# line_follower.net
KiCad netlist of a schematic drawn in EAGLE
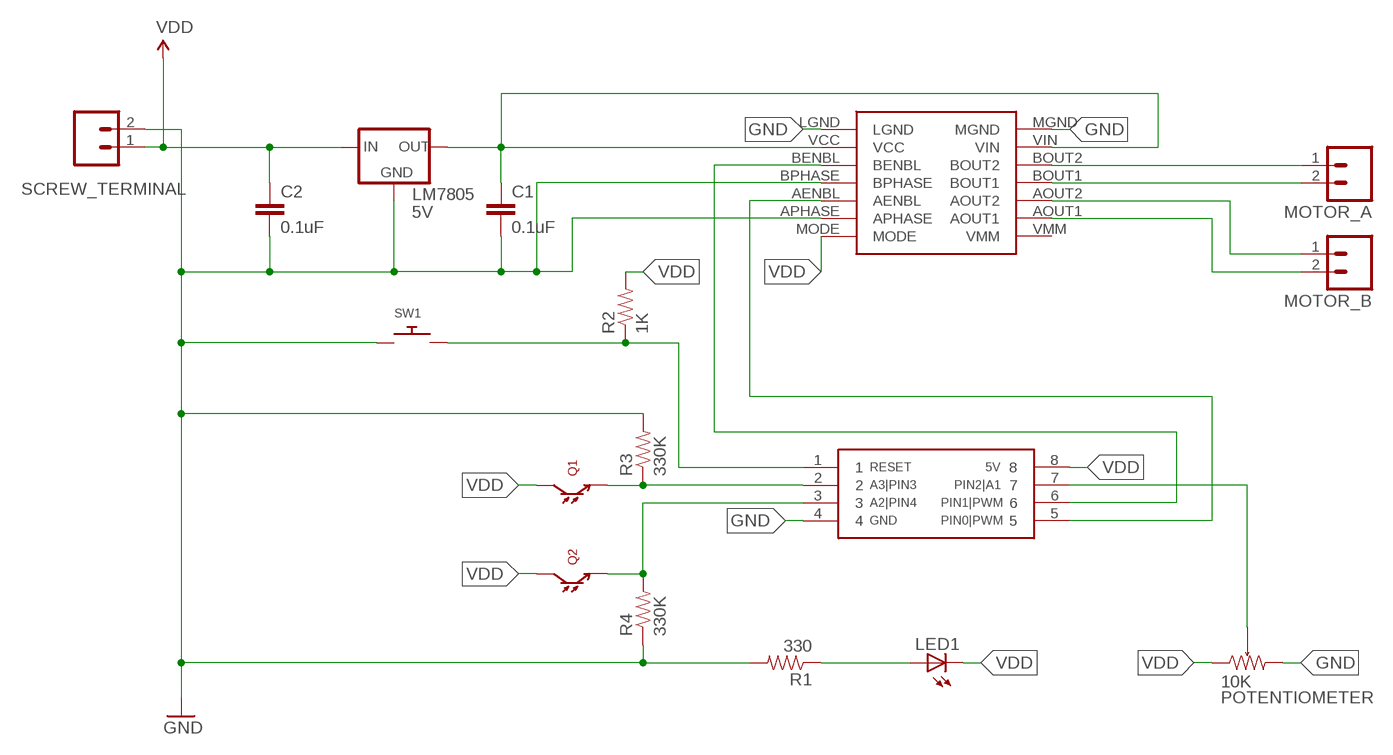
[diagram p0: schematic, sheet 1]

(export (version "E")
  (design (tool "Eeschema 10.0.6"))
  (components
    (comp (ref "10K")
      (value "POTENTIOMETER")
      (footprint "eagle-import:0603-ARV")
      (libsource (lib "eagle-import") (part "POTENTIOMETER"))
    )
    (comp (ref "ATTINY85")
      (value "ATTINY85")
      (footprint "eagle-import:ATTINY_DIP")
      (libsource (lib "eagle-import") (part "ATTINY85"))
    )
    (comp (ref "C1")
      (value "0.1uF")
      (footprint "eagle-import:CAP-PTH-SMALLEZ")
      (libsource (lib "eagle-import") (part "CAPEZ"))
    )
    (comp (ref "C2")
      (value "0.1uF")
      (footprint "eagle-import:CAP-PTH-SMALLEZ")
      (libsource (lib "eagle-import") (part "CAPEZ"))
    )
    (comp (ref "DRV8835")
      (value "POLOLU_MOTOR_DRV8835THROUGHHOLE")
      (footprint "eagle-import:POLOLU_MOTOR_DRV_DRV8835")
      (libsource (lib "eagle-import") (part "POLOLU_MOTOR_DRV8835THROUGHHOLE"))
    )
    (comp (ref "LED1")
      (value "LED5MM")
      (footprint "eagle-import:LED5MM")
      (libsource (lib "eagle-import") (part "LED5MM"))
    )
    (comp (ref "LM7805")
      (value "5V")
      (footprint "eagle-import:78XXS")
      (libsource (lib "eagle-import") (part "78XXS"))
    )
    (comp (ref "MOTOR_A")
      (value "M02PTH")
      (footprint "eagle-import:1X02")
      (libsource (lib "eagle-import") (part "M02PTH"))
    )
    (comp (ref "MOTOR_B")
      (value "M02PTH")
      (footprint "eagle-import:1X02")
      (libsource (lib "eagle-import") (part "M02PTH"))
    )
    (comp (ref "Q1")
      (value "LTR-301")
      (footprint "eagle-import:LTR-301")
      (libsource (lib "eagle-import") (part "LTR-301"))
    )
    (comp (ref "Q2")
      (value "LTR-301")
      (footprint "eagle-import:LTR-301")
      (libsource (lib "eagle-import") (part "LTR-301"))
    )
    (comp (ref "R1")
      (value "330")
      (footprint "eagle-import:AXIAL-0.3EZ")
      (libsource (lib "eagle-import") (part "RESISTOREZ"))
    )
    (comp (ref "R2")
      (value "1K")
      (footprint "eagle-import:AXIAL-0.3EZ")
      (libsource (lib "eagle-import") (part "RESISTOREZ"))
    )
    (comp (ref "R3")
      (value "330K")
      (footprint "eagle-import:AXIAL-0.3EZ")
      (libsource (lib "eagle-import") (part "RESISTOREZ"))
    )
    (comp (ref "R4")
      (value "330K")
      (footprint "eagle-import:AXIAL-0.3EZ")
      (libsource (lib "eagle-import") (part "RESISTOREZ"))
    )
    (comp (ref "SCREW_TERMINAL")
      (value "M02JST-PTH-VERT")
      (footprint "eagle-import:JST-2-PTH-VERT")
      (libsource (lib "eagle-import") (part "M02JST-PTH-VERT"))
    )
    (comp (ref "SW1")
      (value "SWITCH_PUSHBUTTONEVQ-PE")
      (footprint "eagle-import:TACT_PANA-EVQ")
      (libsource (lib "eagle-import") (part "SWITCH_PUSHBUTTONEVQ-PE"))
    )
  )
  (nets
    (net (code "1") (name "GND") (class "Default")
      (node (ref "10K") (pin "2") (pinfunction "2_2") (pintype "passive"))
      (node (ref "ATTINY85") (pin "4") (pinfunction "4_4") (pintype "bidirectional"))
      (node (ref "C1") (pin "2") (pinfunction "2_2") (pintype "passive"))
      (node (ref "C2") (pin "2") (pinfunction "2_2") (pintype "passive"))
      (node (ref "DRV8835") (pin "APHASE") (pinfunction "APHASE_APHASE") (pintype "bidirectional"))
      (node (ref "DRV8835") (pin "BPHASE") (pinfunction "BPHASE_BPHASE") (pintype "bidirectional"))
      (node (ref "DRV8835") (pin "LGND") (pinfunction "LGND_LGND") (pintype "bidirectional"))
      (node (ref "DRV8835") (pin "MGND") (pinfunction "MGND_MGND") (pintype "bidirectional"))
      (node (ref "LM7805") (pin "GND") (pinfunction "GND_GND") (pintype "input"))
      (node (ref "R1") (pin "P$2") (pinfunction "2_P$2") (pintype "passive"))
      (node (ref "R3") (pin "P$2") (pinfunction "2_P$2") (pintype "passive"))
      (node (ref "R4") (pin "P$1") (pinfunction "1_P$1") (pintype "passive"))
      (node (ref "SCREW_TERMINAL") (pin "2") (pinfunction "2_2") (pintype "passive"))
      (node (ref "SW1") (pin "P$1") (pinfunction "P$1_P$1") (pintype "passive"))
    )
    (net (code "2") (name "Net-(10K-P$1-Pad3)") (class "Default")
      (node (ref "10K") (pin "3") (pinfunction "P$1_3") (pintype "bidirectional"))
      (node (ref "10K") (pin "4") (pinfunction "P$1_4") (pintype "bidirectional"))
      (node (ref "10K") (pin "5") (pinfunction "P$1_5") (pintype "bidirectional"))
      (node (ref "10K") (pin "6") (pinfunction "P$1_6") (pintype "bidirectional"))
      (node (ref "10K") (pin "7") (pinfunction "P$1_7") (pintype "bidirectional"))
      (node (ref "10K") (pin "8") (pinfunction "P$1_8") (pintype "bidirectional"))
      (node (ref "ATTINY85") (pin "7") (pinfunction "7_7") (pintype "bidirectional"))
    )
    (net (code "3") (name "Net-(ATTINY85-Pad5)") (class "Default")
      (node (ref "ATTINY85") (pin "5") (pinfunction "5_5") (pintype "bidirectional"))
      (node (ref "DRV8835") (pin "AENBL") (pinfunction "AENBL_AENBL") (pintype "bidirectional"))
    )
    (net (code "4") (name "Net-(ATTINY85-Pad6)") (class "Default")
      (node (ref "ATTINY85") (pin "6") (pinfunction "6_6") (pintype "bidirectional"))
      (node (ref "DRV8835") (pin "BENBL") (pinfunction "BENBL_BENBL") (pintype "bidirectional"))
    )
    (net (code "5") (name "Net-(DRV8835-PadAOUT1)") (class "Default")
      (node (ref "DRV8835") (pin "AOUT1") (pinfunction "AOUT1_AOUT1") (pintype "bidirectional"))
      (node (ref "MOTOR_B") (pin "2") (pinfunction "2_2") (pintype "passive"))
    )
    (net (code "6") (name "Net-(DRV8835-PadAOUT2)") (class "Default")
      (node (ref "DRV8835") (pin "AOUT2") (pinfunction "AOUT2_AOUT2") (pintype "bidirectional"))
      (node (ref "MOTOR_B") (pin "1") (pinfunction "1_1") (pintype "passive"))
    )
    (net (code "7") (name "Net-(DRV8835-PadBOUT1)") (class "Default")
      (node (ref "DRV8835") (pin "BOUT1") (pinfunction "BOUT1_BOUT1") (pintype "bidirectional"))
      (node (ref "MOTOR_A") (pin "2") (pinfunction "2_2") (pintype "passive"))
    )
    (net (code "8") (name "Net-(DRV8835-PadBOUT2)") (class "Default")
      (node (ref "DRV8835") (pin "BOUT2") (pinfunction "BOUT2_BOUT2") (pintype "bidirectional"))
      (node (ref "MOTOR_A") (pin "1") (pinfunction "1_1") (pintype "passive"))
    )
    (net (code "9") (name "Net-(R1-1)") (class "Default")
      (node (ref "LED1") (pin "A") (pinfunction "A_A") (pintype "passive"))
      (node (ref "R1") (pin "P$1") (pinfunction "1_P$1") (pintype "passive"))
    )
    (net (code "10") (name "Net-(R2-1)") (class "Default")
      (node (ref "ATTINY85") (pin "1") (pinfunction "1_1") (pintype "bidirectional"))
      (node (ref "R2") (pin "P$1") (pinfunction "1_P$1") (pintype "passive"))
      (node (ref "SW1") (pin "P$2") (pinfunction "P$2_P$2") (pintype "passive"))
    )
    (net (code "11") (name "Net-(R3-1)") (class "Default")
      (node (ref "ATTINY85") (pin "2") (pinfunction "2_2") (pintype "bidirectional"))
      (node (ref "Q1") (pin "E") (pinfunction "E_E") (pintype "bidirectional"))
      (node (ref "R3") (pin "P$1") (pinfunction "1_P$1") (pintype "passive"))
    )
    (net (code "12") (name "Net-(R4-2)") (class "Default")
      (node (ref "ATTINY85") (pin "3") (pinfunction "3_3") (pintype "bidirectional"))
      (node (ref "Q2") (pin "E") (pinfunction "E_E") (pintype "bidirectional"))
      (node (ref "R4") (pin "P$2") (pinfunction "2_P$2") (pintype "passive"))
    )
    (net (code "13") (name "VDD") (class "Default")
      (node (ref "10K") (pin "1") (pinfunction "1_1") (pintype "passive"))
      (node (ref "ATTINY85") (pin "8") (pinfunction "8_8") (pintype "bidirectional"))
      (node (ref "C1") (pin "1") (pinfunction "1_1") (pintype "passive"))
      (node (ref "C2") (pin "1") (pinfunction "1_1") (pintype "passive"))
      (node (ref "DRV8835") (pin "MODE") (pinfunction "MODE_MODE") (pintype "bidirectional"))
      (node (ref "DRV8835") (pin "VCC") (pinfunction "VCC_VCC") (pintype "bidirectional"))
      (node (ref "DRV8835") (pin "VIN") (pinfunction "VIN_VIN") (pintype "bidirectional"))
      (node (ref "LED1") (pin "K") (pinfunction "C_K") (pintype "passive"))
      (node (ref "LM7805") (pin "IN") (pinfunction "IN_IN") (pintype "input"))
      (node (ref "LM7805") (pin "OUT") (pinfunction "OUT_OUT") (pintype "passive"))
      (node (ref "Q1") (pin "C") (pinfunction "C_C") (pintype "bidirectional"))
      (node (ref "Q2") (pin "C") (pinfunction "C_C") (pintype "bidirectional"))
      (node (ref "R2") (pin "P$2") (pinfunction "2_P$2") (pintype "passive"))
      (node (ref "SCREW_TERMINAL") (pin "1") (pinfunction "1_1") (pintype "passive"))
    )
    (net (code "14") (name "unconnected-(DRV8835-PadVMM)") (class "Default")
      (node (ref "DRV8835") (pin "VMM") (pinfunction "VMM_VMM") (pintype "bidirectional"))
    )
  )
)
